# Amplifiers2.net
KiCad netlist of a schematic drawn in Altium Designer
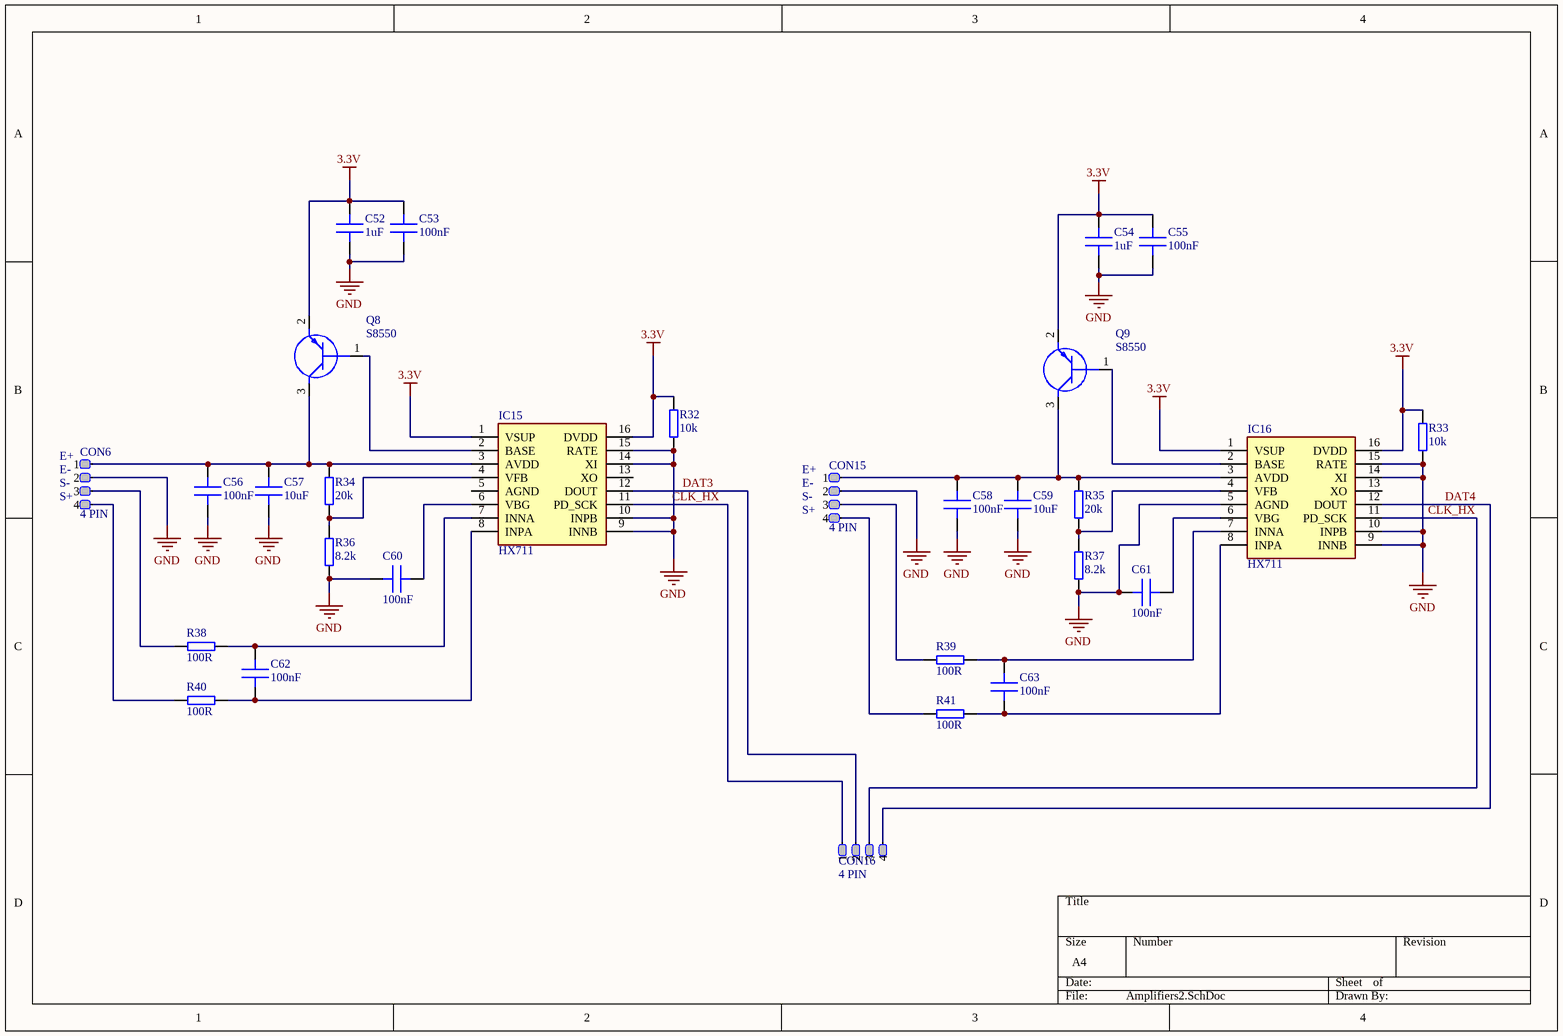
[diagram p0: Amplifiers2.SchDoc]

(export (version "E")
  (design (tool "Eeschema 10.0.6"))
  (components
    (comp (ref "C52")
      (value "1uF")
      (footprint "C 0402")
      (description "MLCC Capacitor")
      (libsource (lib "Components") (part "Capacitor"))
    )
    (comp (ref "C53")
      (value "100nF")
      (footprint "C 0402")
      (description "MLCC Capacitor")
      (libsource (lib "Components") (part "Capacitor"))
    )
    (comp (ref "C54")
      (value "1uF")
      (footprint "C 0402")
      (description "MLCC Capacitor")
      (libsource (lib "Components") (part "Capacitor"))
    )
    (comp (ref "C55")
      (value "100nF")
      (footprint "C 0402")
      (description "MLCC Capacitor")
      (libsource (lib "Components") (part "Capacitor"))
    )
    (comp (ref "C56")
      (value "100nF")
      (footprint "C 0402")
      (description "MLCC Capacitor")
      (libsource (lib "Components") (part "Capacitor"))
    )
    (comp (ref "C57")
      (value "10uF")
      (footprint "C 0402")
      (description "MLCC Capacitor")
      (libsource (lib "Components") (part "Capacitor"))
    )
    (comp (ref "C58")
      (value "100nF")
      (footprint "C 0402")
      (description "MLCC Capacitor")
      (libsource (lib "Components") (part "Capacitor"))
    )
    (comp (ref "C59")
      (value "10uF")
      (footprint "C 0402")
      (description "MLCC Capacitor")
      (libsource (lib "Components") (part "Capacitor"))
    )
    (comp (ref "C60")
      (value "100nF")
      (footprint "C 0402")
      (description "MLCC Capacitor")
      (libsource (lib "Components") (part "Capacitor"))
    )
    (comp (ref "C61")
      (value "100nF")
      (footprint "C 0402")
      (description "MLCC Capacitor")
      (libsource (lib "Components") (part "Capacitor"))
    )
    (comp (ref "C62")
      (value "100nF")
      (footprint "C 0402")
      (description "MLCC Capacitor")
      (libsource (lib "Components") (part "Capacitor"))
    )
    (comp (ref "C63")
      (value "100nF")
      (footprint "C 0402")
      (description "MLCC Capacitor")
      (libsource (lib "Components") (part "Capacitor"))
    )
    (comp (ref "CON6")
      (value "4 PIN")
      (footprint "BM04B-SRSS-TB")
      (libsource (lib "Connectors") (part "4 PIN"))
    )
    (comp (ref "CON15")
      (value "4 PIN")
      (footprint "BM04B-SRSS-TB")
      (libsource (lib "Connectors") (part "4 PIN"))
    )
    (comp (ref "CON16")
      (value "4 PIN")
      (footprint "Goldpin 1.27mm 4PIN")
      (libsource (lib "Connectors") (part "4 PIN"))
    )
    (comp (ref "IC15")
      (value "HX711")
      (footprint "SamacSys:SOIC127P600X160-16N")
      (description "Integrated Circuit")
      (libsource (lib "caravan_sch_lib") (part "HX711"))
    )
    (comp (ref "IC16")
      (value "HX711")
      (footprint "SamacSys:SOIC127P600X160-16N")
      (description "Integrated Circuit")
      (libsource (lib "caravan_sch_lib") (part "HX711"))
    )
    (comp (ref "Q8")
      (value "S8550")
      (footprint "SamacSys:SOT95P240X110-3N")
      (description "Transistor BJT PNP")
      (libsource (lib "*") (part "S8550"))
    )
    (comp (ref "Q9")
      (value "S8550")
      (footprint "SamacSys:SOT95P240X110-3N")
      (description "Transistor BJT PNP")
      (libsource (lib "*") (part "S8550"))
    )
    (comp (ref "R32")
      (value "10k")
      (footprint "R 0402")
      (description "General pourpouse resistor")
      (libsource (lib "Components") (part "Resistor"))
    )
    (comp (ref "R33")
      (value "10k")
      (footprint "R 0402")
      (description "General pourpouse resistor")
      (libsource (lib "Components") (part "Resistor"))
    )
    (comp (ref "R34")
      (value "20k")
      (footprint "R 0402")
      (description "General pourpouse resistor")
      (libsource (lib "Components") (part "Resistor"))
    )
    (comp (ref "R35")
      (value "20k")
      (footprint "R 0402")
      (description "General pourpouse resistor")
      (libsource (lib "Components") (part "Resistor"))
    )
    (comp (ref "R36")
      (value "8.2k")
      (footprint "R 0402")
      (description "General pourpouse resistor")
      (libsource (lib "Components") (part "Resistor"))
    )
    (comp (ref "R37")
      (value "8.2k")
      (footprint "R 0402")
      (description "General pourpouse resistor")
      (libsource (lib "Components") (part "Resistor"))
    )
    (comp (ref "R38")
      (value "100R")
      (footprint "R 0402")
      (description "General pourpouse resistor")
      (libsource (lib "Components") (part "Resistor"))
    )
    (comp (ref "R39")
      (value "100R")
      (footprint "R 0402")
      (description "General pourpouse resistor")
      (libsource (lib "Components") (part "Resistor"))
    )
    (comp (ref "R40")
      (value "100R")
      (footprint "R 0402")
      (description "General pourpouse resistor")
      (libsource (lib "Components") (part "Resistor"))
    )
    (comp (ref "R41")
      (value "100R")
      (footprint "R 0402")
      (description "General pourpouse resistor")
      (libsource (lib "Components") (part "Resistor"))
    )
  )
  (nets
    (net (code "1") (name "/CLK_HX") (class "Default")
      (node (ref "CON16") (pin "1") (pinfunction "1_1") (pintype "passive"))
      (node (ref "CON16") (pin "3") (pinfunction "3_3") (pintype "passive"))
      (node (ref "IC15") (pin "11") (pinfunction "PD_SCK_11") (pintype "passive"))
      (node (ref "IC16") (pin "11") (pinfunction "PD_SCK_11") (pintype "passive"))
    )
    (net (code "2") (name "/DAT3") (class "Default")
      (node (ref "CON16") (pin "2") (pinfunction "2_2") (pintype "passive"))
      (node (ref "IC15") (pin "12") (pinfunction "DOUT_12") (pintype "passive"))
    )
    (net (code "3") (name "/DAT4") (class "Default")
      (node (ref "CON16") (pin "4") (pinfunction "4_4") (pintype "passive"))
      (node (ref "IC16") (pin "12") (pinfunction "DOUT_12") (pintype "passive"))
    )
    (net (code "4") (name "3.3V") (class "Default")
      (node (ref "C52") (pin "1") (pinfunction "1_1") (pintype "passive"))
      (node (ref "C53") (pin "1") (pinfunction "1_1") (pintype "passive"))
      (node (ref "C54") (pin "1") (pinfunction "1_1") (pintype "passive"))
      (node (ref "C55") (pin "1") (pinfunction "1_1") (pintype "passive"))
      (node (ref "IC15") (pin "1") (pinfunction "VSUP_1") (pintype "passive"))
      (node (ref "IC15") (pin "16") (pinfunction "DVDD_16") (pintype "passive"))
      (node (ref "IC16") (pin "1") (pinfunction "VSUP_1") (pintype "passive"))
      (node (ref "IC16") (pin "16") (pinfunction "DVDD_16") (pintype "passive"))
      (node (ref "Q8") (pin "2") (pinfunction "E_2") (pintype "passive"))
      (node (ref "Q9") (pin "2") (pinfunction "E_2") (pintype "passive"))
      (node (ref "R32") (pin "2") (pinfunction "2_2") (pintype "passive"))
      (node (ref "R33") (pin "2") (pinfunction "2_2") (pintype "passive"))
    )
    (net (code "5") (name "GND") (class "Default")
      (node (ref "C52") (pin "2") (pinfunction "2_2") (pintype "passive"))
      (node (ref "C53") (pin "2") (pinfunction "2_2") (pintype "passive"))
      (node (ref "C54") (pin "2") (pinfunction "2_2") (pintype "passive"))
      (node (ref "C55") (pin "2") (pinfunction "2_2") (pintype "passive"))
      (node (ref "C56") (pin "2") (pinfunction "2_2") (pintype "passive"))
      (node (ref "C57") (pin "2") (pinfunction "2_2") (pintype "passive"))
      (node (ref "C58") (pin "2") (pinfunction "2_2") (pintype "passive"))
      (node (ref "C59") (pin "2") (pinfunction "2_2") (pintype "passive"))
      (node (ref "C60") (pin "1") (pinfunction "1_1") (pintype "passive"))
      (node (ref "C61") (pin "1") (pinfunction "1_1") (pintype "passive"))
      (node (ref "CON15") (pin "2") (pinfunction "2_2") (pintype "passive"))
      (node (ref "CON6") (pin "2") (pinfunction "2_2") (pintype "passive"))
      (node (ref "IC15") (pin "10") (pinfunction "INPB_10") (pintype "passive"))
      (node (ref "IC15") (pin "14") (pinfunction "XI_14") (pintype "passive"))
      (node (ref "IC15") (pin "15") (pinfunction "RATE_15") (pintype "passive"))
      (node (ref "IC15") (pin "9") (pinfunction "INNB_9") (pintype "passive"))
      (node (ref "IC16") (pin "10") (pinfunction "INPB_10") (pintype "passive"))
      (node (ref "IC16") (pin "14") (pinfunction "XI_14") (pintype "passive"))
      (node (ref "IC16") (pin "15") (pinfunction "RATE_15") (pintype "passive"))
      (node (ref "IC16") (pin "5") (pinfunction "AGND_5") (pintype "passive"))
      (node (ref "IC16") (pin "9") (pinfunction "INNB_9") (pintype "passive"))
      (node (ref "R32") (pin "1") (pinfunction "1_1") (pintype "passive"))
      (node (ref "R33") (pin "1") (pinfunction "1_1") (pintype "passive"))
      (node (ref "R36") (pin "1") (pinfunction "1_1") (pintype "passive"))
      (node (ref "R37") (pin "1") (pinfunction "1_1") (pintype "passive"))
    )
    (net (code "6") (name "Net-(CON6-Pad3)") (class "Default")
      (node (ref "CON6") (pin "3") (pinfunction "3_3") (pintype "passive"))
      (node (ref "R38") (pin "2") (pinfunction "2_2") (pintype "passive"))
    )
    (net (code "7") (name "Net-(CON6-Pad4)") (class "Default")
      (node (ref "CON6") (pin "4") (pinfunction "4_4") (pintype "passive"))
      (node (ref "R40") (pin "2") (pinfunction "2_2") (pintype "passive"))
    )
    (net (code "8") (name "Net-(CON15-Pad3)") (class "Default")
      (node (ref "CON15") (pin "3") (pinfunction "3_3") (pintype "passive"))
      (node (ref "R39") (pin "2") (pinfunction "2_2") (pintype "passive"))
    )
    (net (code "9") (name "Net-(CON15-Pad4)") (class "Default")
      (node (ref "CON15") (pin "4") (pinfunction "4_4") (pintype "passive"))
      (node (ref "R41") (pin "2") (pinfunction "2_2") (pintype "passive"))
    )
    (net (code "10") (name "Net-(IC15-AVDD)") (class "Default")
      (node (ref "C56") (pin "1") (pinfunction "1_1") (pintype "passive"))
      (node (ref "C57") (pin "1") (pinfunction "1_1") (pintype "passive"))
      (node (ref "CON6") (pin "1") (pinfunction "1_1") (pintype "passive"))
      (node (ref "IC15") (pin "3") (pinfunction "AVDD_3") (pintype "passive"))
      (node (ref "Q8") (pin "3") (pinfunction "C_3") (pintype "passive"))
      (node (ref "R34") (pin "2") (pinfunction "2_2") (pintype "passive"))
    )
    (net (code "11") (name "Net-(IC15-BASE)") (class "Default")
      (node (ref "IC15") (pin "2") (pinfunction "BASE_2") (pintype "passive"))
      (node (ref "Q8") (pin "1") (pinfunction "B_1") (pintype "passive"))
    )
    (net (code "12") (name "Net-(IC15-INNA)") (class "Default")
      (node (ref "C62") (pin "2") (pinfunction "2_2") (pintype "passive"))
      (node (ref "IC15") (pin "7") (pinfunction "INNA_7") (pintype "passive"))
      (node (ref "R38") (pin "1") (pinfunction "1_1") (pintype "passive"))
    )
    (net (code "13") (name "Net-(IC15-INPA)") (class "Default")
      (node (ref "C62") (pin "1") (pinfunction "1_1") (pintype "passive"))
      (node (ref "IC15") (pin "8") (pinfunction "INPA_8") (pintype "passive"))
      (node (ref "R40") (pin "1") (pinfunction "1_1") (pintype "passive"))
    )
    (net (code "14") (name "Net-(IC15-VBG)") (class "Default")
      (node (ref "C60") (pin "2") (pinfunction "2_2") (pintype "passive"))
      (node (ref "IC15") (pin "6") (pinfunction "VBG_6") (pintype "passive"))
    )
    (net (code "15") (name "Net-(IC15-VFB)") (class "Default")
      (node (ref "IC15") (pin "4") (pinfunction "VFB_4") (pintype "passive"))
      (node (ref "R34") (pin "1") (pinfunction "1_1") (pintype "passive"))
      (node (ref "R36") (pin "2") (pinfunction "2_2") (pintype "passive"))
    )
    (net (code "16") (name "Net-(IC16-AVDD)") (class "Default")
      (node (ref "C58") (pin "1") (pinfunction "1_1") (pintype "passive"))
      (node (ref "C59") (pin "1") (pinfunction "1_1") (pintype "passive"))
      (node (ref "CON15") (pin "1") (pinfunction "1_1") (pintype "passive"))
      (node (ref "IC16") (pin "3") (pinfunction "AVDD_3") (pintype "passive"))
      (node (ref "Q9") (pin "3") (pinfunction "C_3") (pintype "passive"))
      (node (ref "R35") (pin "2") (pinfunction "2_2") (pintype "passive"))
    )
    (net (code "17") (name "Net-(IC16-BASE)") (class "Default")
      (node (ref "IC16") (pin "2") (pinfunction "BASE_2") (pintype "passive"))
      (node (ref "Q9") (pin "1") (pinfunction "B_1") (pintype "passive"))
    )
    (net (code "18") (name "Net-(IC16-INNA)") (class "Default")
      (node (ref "C63") (pin "2") (pinfunction "2_2") (pintype "passive"))
      (node (ref "IC16") (pin "7") (pinfunction "INNA_7") (pintype "passive"))
      (node (ref "R39") (pin "1") (pinfunction "1_1") (pintype "passive"))
    )
    (net (code "19") (name "Net-(IC16-INPA)") (class "Default")
      (node (ref "C63") (pin "1") (pinfunction "1_1") (pintype "passive"))
      (node (ref "IC16") (pin "8") (pinfunction "INPA_8") (pintype "passive"))
      (node (ref "R41") (pin "1") (pinfunction "1_1") (pintype "passive"))
    )
    (net (code "20") (name "Net-(IC16-VBG)") (class "Default")
      (node (ref "C61") (pin "2") (pinfunction "2_2") (pintype "passive"))
      (node (ref "IC16") (pin "6") (pinfunction "VBG_6") (pintype "passive"))
    )
    (net (code "21") (name "Net-(IC16-VFB)") (class "Default")
      (node (ref "IC16") (pin "4") (pinfunction "VFB_4") (pintype "passive"))
      (node (ref "R35") (pin "1") (pinfunction "1_1") (pintype "passive"))
      (node (ref "R37") (pin "2") (pinfunction "2_2") (pintype "passive"))
    )
    (net (code "22") (name "unconnected-(IC15-AGND-Pad5)") (class "Default")
      (node (ref "IC15") (pin "5") (pinfunction "AGND_5") (pintype "passive"))
    )
    (net (code "23") (name "unconnected-(IC15-XO-Pad13)") (class "Default")
      (node (ref "IC15") (pin "13") (pinfunction "XO_13") (pintype "passive"))
    )
    (net (code "24") (name "unconnected-(IC16-XO-Pad13)") (class "Default")
      (node (ref "IC16") (pin "13") (pinfunction "XO_13") (pintype "passive"))
    )
  )
)
